# Stick.net
KiCad netlist of a schematic drawn in Altium Designer
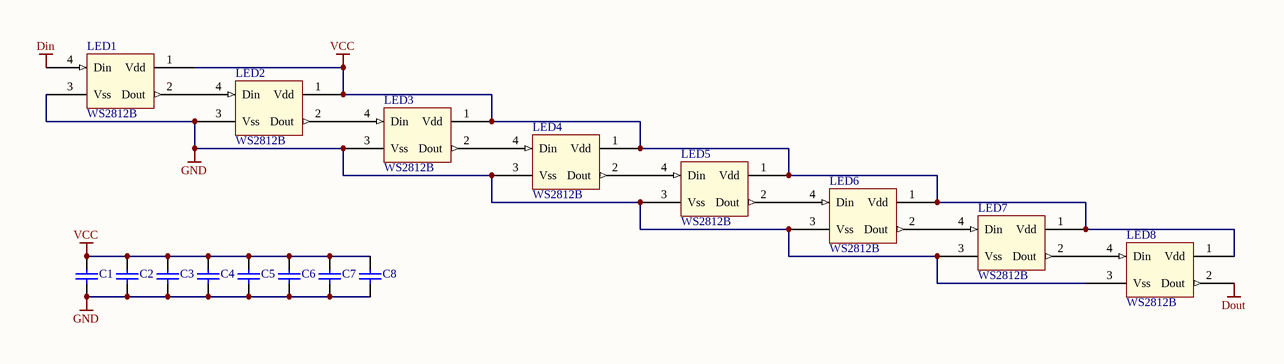
[diagram p0: Stick.SchDoc]

(export (version "E")
  (design (tool "Eeschema 10.0.6"))
  (components
    (comp (ref "C1")
      (value "~")
      (footprint "C1206")
      (description "Capacitor")
      (fields (field (name "PUBLISHER") "Altium Limited"))
      (libsource (lib "Miscellaneous Devices") (part "Cap"))
    )
    (comp (ref "C2")
      (value "~")
      (footprint "C1206")
      (description "Capacitor")
      (fields (field (name "PUBLISHER") "Altium Limited"))
      (libsource (lib "Miscellaneous Devices") (part "Cap"))
    )
    (comp (ref "C3")
      (value "~")
      (footprint "C1206")
      (description "Capacitor")
      (fields (field (name "PUBLISHER") "Altium Limited"))
      (libsource (lib "Miscellaneous Devices") (part "Cap"))
    )
    (comp (ref "C4")
      (value "~")
      (footprint "C1206")
      (description "Capacitor")
      (fields (field (name "PUBLISHER") "Altium Limited"))
      (libsource (lib "Miscellaneous Devices") (part "Cap"))
    )
    (comp (ref "C5")
      (value "~")
      (footprint "C1206")
      (description "Capacitor")
      (fields (field (name "PUBLISHER") "Altium Limited"))
      (libsource (lib "Miscellaneous Devices") (part "Cap"))
    )
    (comp (ref "C6")
      (value "~")
      (footprint "C1206")
      (description "Capacitor")
      (fields (field (name "PUBLISHER") "Altium Limited"))
      (libsource (lib "Miscellaneous Devices") (part "Cap"))
    )
    (comp (ref "C7")
      (value "~")
      (footprint "C1206")
      (description "Capacitor")
      (fields (field (name "PUBLISHER") "Altium Limited"))
      (libsource (lib "Miscellaneous Devices") (part "Cap"))
    )
    (comp (ref "C8")
      (value "~")
      (footprint "C1206")
      (description "Capacitor")
      (fields (field (name "PUBLISHER") "Altium Limited"))
      (libsource (lib "Miscellaneous Devices") (part "Cap"))
    )
    (comp (ref "LED1") (value "WS2812B") (footprint "WS2812B") (libsource (lib "WS2812") (part "WS2812B")))
    (comp (ref "LED2") (value "WS2812B") (footprint "WS2812B") (libsource (lib "WS2812") (part "WS2812B")))
    (comp (ref "LED3") (value "WS2812B") (footprint "WS2812B") (libsource (lib "WS2812") (part "WS2812B")))
    (comp (ref "LED4") (value "WS2812B") (footprint "WS2812B") (libsource (lib "WS2812") (part "WS2812B")))
    (comp (ref "LED5") (value "WS2812B") (footprint "WS2812B") (libsource (lib "WS2812") (part "WS2812B")))
    (comp (ref "LED6") (value "WS2812B") (footprint "WS2812B") (libsource (lib "WS2812") (part "WS2812B")))
    (comp (ref "LED7") (value "WS2812B") (footprint "WS2812B") (libsource (lib "WS2812") (part "WS2812B")))
    (comp (ref "LED8") (value "WS2812B") (footprint "WS2812B") (libsource (lib "WS2812") (part "WS2812B")))
  )
  (nets
    (net (code "1") (name "Din") (class "Default")
      (node (ref "LED1") (pin "4") (pinfunction "Din_4") (pintype "input"))
    )
    (net (code "2") (name "Dout") (class "Default")
      (node (ref "LED8") (pin "2") (pinfunction "Dout_2") (pintype "output"))
    )
    (net (code "3") (name "GND") (class "Default")
      (node (ref "C1") (pin "1") (pinfunction "1_1") (pintype "passive"))
      (node (ref "C2") (pin "1") (pinfunction "1_1") (pintype "passive"))
      (node (ref "C3") (pin "1") (pinfunction "1_1") (pintype "passive"))
      (node (ref "C4") (pin "1") (pinfunction "1_1") (pintype "passive"))
      (node (ref "C5") (pin "1") (pinfunction "1_1") (pintype "passive"))
      (node (ref "C6") (pin "1") (pinfunction "1_1") (pintype "passive"))
      (node (ref "C7") (pin "1") (pinfunction "1_1") (pintype "passive"))
      (node (ref "C8") (pin "1") (pinfunction "1_1") (pintype "passive"))
      (node (ref "LED1") (pin "3") (pinfunction "Vss_3") (pintype "power_in"))
      (node (ref "LED2") (pin "3") (pinfunction "Vss_3") (pintype "power_in"))
      (node (ref "LED3") (pin "3") (pinfunction "Vss_3") (pintype "power_in"))
      (node (ref "LED4") (pin "3") (pinfunction "Vss_3") (pintype "power_in"))
      (node (ref "LED5") (pin "3") (pinfunction "Vss_3") (pintype "power_in"))
      (node (ref "LED6") (pin "3") (pinfunction "Vss_3") (pintype "power_in"))
      (node (ref "LED7") (pin "3") (pinfunction "Vss_3") (pintype "power_in"))
      (node (ref "LED8") (pin "3") (pinfunction "Vss_3") (pintype "power_in"))
    )
    (net (code "4") (name "Net-(LED1-Dout)") (class "Default")
      (node (ref "LED1") (pin "2") (pinfunction "Dout_2") (pintype "output"))
      (node (ref "LED2") (pin "4") (pinfunction "Din_4") (pintype "input"))
    )
    (net (code "5") (name "Net-(LED2-Dout)") (class "Default")
      (node (ref "LED2") (pin "2") (pinfunction "Dout_2") (pintype "output"))
      (node (ref "LED3") (pin "4") (pinfunction "Din_4") (pintype "input"))
    )
    (net (code "6") (name "Net-(LED3-Dout)") (class "Default")
      (node (ref "LED3") (pin "2") (pinfunction "Dout_2") (pintype "output"))
      (node (ref "LED4") (pin "4") (pinfunction "Din_4") (pintype "input"))
    )
    (net (code "7") (name "Net-(LED4-Dout)") (class "Default")
      (node (ref "LED4") (pin "2") (pinfunction "Dout_2") (pintype "output"))
      (node (ref "LED5") (pin "4") (pinfunction "Din_4") (pintype "input"))
    )
    (net (code "8") (name "Net-(LED5-Dout)") (class "Default")
      (node (ref "LED5") (pin "2") (pinfunction "Dout_2") (pintype "output"))
      (node (ref "LED6") (pin "4") (pinfunction "Din_4") (pintype "input"))
    )
    (net (code "9") (name "Net-(LED6-Dout)") (class "Default")
      (node (ref "LED6") (pin "2") (pinfunction "Dout_2") (pintype "output"))
      (node (ref "LED7") (pin "4") (pinfunction "Din_4") (pintype "input"))
    )
    (net (code "10") (name "Net-(LED7-Dout)") (class "Default")
      (node (ref "LED7") (pin "2") (pinfunction "Dout_2") (pintype "output"))
      (node (ref "LED8") (pin "4") (pinfunction "Din_4") (pintype "input"))
    )
    (net (code "11") (name "VCC") (class "Default")
      (node (ref "C1") (pin "2") (pinfunction "2_2") (pintype "passive"))
      (node (ref "C2") (pin "2") (pinfunction "2_2") (pintype "passive"))
      (node (ref "C3") (pin "2") (pinfunction "2_2") (pintype "passive"))
      (node (ref "C4") (pin "2") (pinfunction "2_2") (pintype "passive"))
      (node (ref "C5") (pin "2") (pinfunction "2_2") (pintype "passive"))
      (node (ref "C6") (pin "2") (pinfunction "2_2") (pintype "passive"))
      (node (ref "C7") (pin "2") (pinfunction "2_2") (pintype "passive"))
      (node (ref "C8") (pin "2") (pinfunction "2_2") (pintype "passive"))
      (node (ref "LED1") (pin "1") (pinfunction "Vdd_1") (pintype "power_in"))
      (node (ref "LED2") (pin "1") (pinfunction "Vdd_1") (pintype "power_in"))
      (node (ref "LED3") (pin "1") (pinfunction "Vdd_1") (pintype "power_in"))
      (node (ref "LED4") (pin "1") (pinfunction "Vdd_1") (pintype "power_in"))
      (node (ref "LED5") (pin "1") (pinfunction "Vdd_1") (pintype "power_in"))
      (node (ref "LED6") (pin "1") (pinfunction "Vdd_1") (pintype "power_in"))
      (node (ref "LED7") (pin "1") (pinfunction "Vdd_1") (pintype "power_in"))
      (node (ref "LED8") (pin "1") (pinfunction "Vdd_1") (pintype "power_in"))
    )
  )
)
